# WifiNode_Pwr.net
KiCad netlist of a schematic drawn in Altium Designer
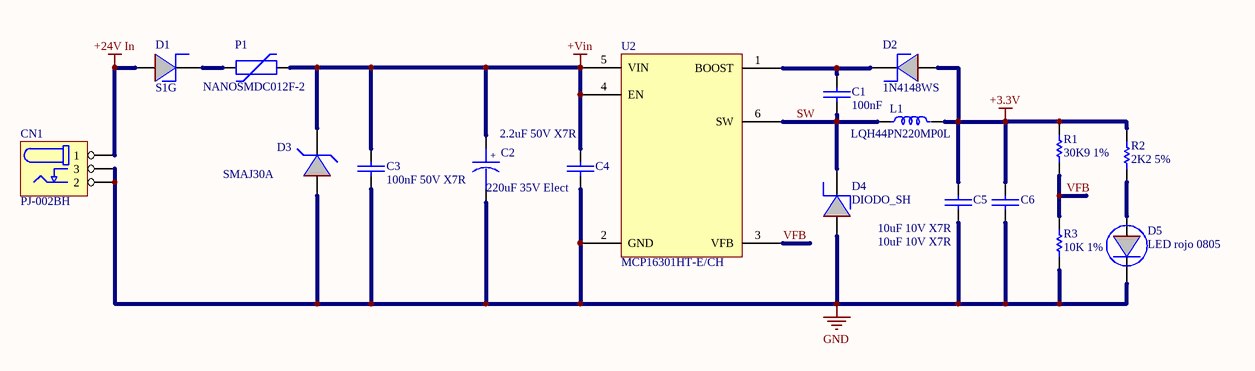
[diagram p0: WifiNode_Pwr.SchDoc]

(export (version "E")
  (design (tool "Eeschema 10.0.6"))
  (components
    (comp (ref "C1")
      (value "100nF")
      (footprint "C_0805")
      (description "Non Polarized Capacitor")
      (libsource (lib "WifiNode") (part "CAP"))
    )
    (comp (ref "C2")
      (value "220uF 35V Elect")
      (footprint "C_RAD_0.135_H_8X12_S")
      (description "Polarized Capacitor")
      (libsource (lib "WifiNode") (part "CAP_P"))
    )
    (comp (ref "C3")
      (value "100nF 50V X7R")
      (footprint "C_0805")
      (description "Non Polarized Capacitor")
      (libsource (lib "WifiNode") (part "CAP"))
    )
    (comp (ref "C4")
      (value "2.2uF 50V X7R")
      (footprint "C_0805")
      (description "Non Polarized Capacitor")
      (libsource (lib "WifiNode") (part "CAP"))
    )
    (comp (ref "C5")
      (value "10uF 10V X7R")
      (footprint "C_0805")
      (description "Non Polarized Capacitor")
      (libsource (lib "WifiNode") (part "CAP"))
    )
    (comp (ref "C6")
      (value "10uF 10V X7R")
      (footprint "C_0805")
      (description "Non Polarized Capacitor")
      (libsource (lib "WifiNode") (part "CAP"))
    )
    (comp (ref "CN1")
      (value "PJ-002BH")
      (footprint "PJ002B")
      (description "Barrel Power Connector")
      (libsource (lib "WifiNode") (part "CN_PowerJack"))
    )
    (comp (ref "D1")
      (value "S1G")
      (footprint "D_SMA")
      (description "Diode Shottky")
      (libsource (lib "") (part "DIODO_SH_1"))
    )
    (comp (ref "D2")
      (value "1N4148WS")
      (footprint "D_SMA")
      (description "Diode Shottky")
      (libsource (lib "WifiNode") (part "DIODO_SH"))
    )
    (comp (ref "D3")
      (value "SMAJ30A")
      (footprint "D_SMA")
      (description "Unidirectional TVS")
      (libsource (lib "WifiNode") (part "DIODE_TVS"))
    )
    (comp (ref "D4")
      (value "DIODO_SH")
      (footprint "D_SMA")
      (description "Diode Shottky")
      (libsource (lib "WifiNode") (part "DIODO_SH"))
    )
    (comp (ref "D5")
      (value "LED rojo 0805")
      (footprint "D_0805")
      (description "LED")
      (libsource (lib "WifiNode") (part "LED"))
    )
    (comp (ref "L1")
      (value "LQH44PN220MP0L")
      (footprint "LQH44")
      (description "Inductor")
      (libsource (lib "WifiNode") (part "IND"))
    )
    (comp (ref "P1")
      (value "NANOSMDC012F-2")
      (footprint "NANOSMDC")
      (description "Polyswitch")
      (libsource (lib "WifiNode") (part "PLYSW"))
    )
    (comp (ref "R1")
      (value "30K9 1%")
      (footprint "R_0805")
      (description "Resistor")
      (libsource (lib "WifiNode") (part "Res1"))
    )
    (comp (ref "R2")
      (value "2K2 5%")
      (footprint "R_0805")
      (description "Resistor")
      (libsource (lib "WifiNode") (part "Res1"))
    )
    (comp (ref "R3")
      (value "10K 1%")
      (footprint "R_0805")
      (description "Resistor")
      (libsource (lib "WifiNode") (part "Res1"))
    )
    (comp (ref "U2")
      (value "MCP16301HT-E/CH")
      (footprint "SOT23-6")
      (description "Buck 36V-adj 600mA SOT-6")
      (libsource (lib "WifiNode") (part "MCP16301"))
    )
  )
  (nets
    (net (code "1") (name "+3.3V") (class "Default")
      (node (ref "C5") (pin "1") (pinfunction "1_1") (pintype "passive"))
      (node (ref "C6") (pin "1") (pinfunction "1_1") (pintype "passive"))
      (node (ref "D2") (pin "1") (pinfunction "A_1") (pintype "passive"))
      (node (ref "L1") (pin "2") (pinfunction "2_2") (pintype "passive"))
      (node (ref "R1") (pin "2") (pinfunction "2_2") (pintype "passive"))
      (node (ref "R2") (pin "2") (pinfunction "2_2") (pintype "passive"))
    )
    (net (code "2") (name "+24V In") (class "Default")
      (node (ref "CN1") (pin "1") (pinfunction "1_1") (pintype "passive"))
      (node (ref "D1") (pin "1") (pinfunction "A_1") (pintype "passive"))
    )
    (net (code "3") (name "+Vin") (class "Default")
      (node (ref "C2") (pin "1") (pinfunction "1_1") (pintype "passive"))
      (node (ref "C3") (pin "1") (pinfunction "1_1") (pintype "passive"))
      (node (ref "C4") (pin "1") (pinfunction "1_1") (pintype "passive"))
      (node (ref "D3") (pin "2") (pinfunction "K_2") (pintype "passive"))
      (node (ref "P1") (pin "2") (pinfunction "2_2") (pintype "passive"))
      (node (ref "U2") (pin "4") (pinfunction "EN_4") (pintype "passive"))
      (node (ref "U2") (pin "5") (pinfunction "VIN_5") (pintype "passive"))
    )
    (net (code "4") (name "/SW") (class "Default")
      (node (ref "C1") (pin "2") (pinfunction "2_2") (pintype "passive"))
      (node (ref "D4") (pin "2") (pinfunction "K_2") (pintype "passive"))
      (node (ref "L1") (pin "1") (pinfunction "1_1") (pintype "passive"))
      (node (ref "U2") (pin "6") (pinfunction "SW_6") (pintype "passive"))
    )
    (net (code "5") (name "/VFB") (class "Default")
      (node (ref "R1") (pin "1") (pinfunction "1_1") (pintype "passive"))
      (node (ref "R3") (pin "2") (pinfunction "2_2") (pintype "passive"))
      (node (ref "U2") (pin "3") (pinfunction "VFB_3") (pintype "passive"))
    )
    (net (code "6") (name "GND") (class "Default")
      (node (ref "C2") (pin "2") (pinfunction "2_2") (pintype "passive"))
      (node (ref "C3") (pin "2") (pinfunction "2_2") (pintype "passive"))
      (node (ref "C4") (pin "2") (pinfunction "2_2") (pintype "passive"))
      (node (ref "C5") (pin "2") (pinfunction "2_2") (pintype "passive"))
      (node (ref "C6") (pin "2") (pinfunction "2_2") (pintype "passive"))
      (node (ref "CN1") (pin "2") (pinfunction "2_2") (pintype "passive"))
      (node (ref "CN1") (pin "3") (pinfunction "3_3") (pintype "passive"))
      (node (ref "D3") (pin "1") (pinfunction "A_1") (pintype "passive"))
      (node (ref "D4") (pin "1") (pinfunction "A_1") (pintype "passive"))
      (node (ref "D5") (pin "2") (pinfunction "K_2") (pintype "passive"))
      (node (ref "R3") (pin "1") (pinfunction "1_1") (pintype "passive"))
      (node (ref "U2") (pin "2") (pinfunction "GND_2") (pintype "passive"))
    )
    (net (code "7") (name "Net-(D1-K)") (class "Default")
      (node (ref "D1") (pin "2") (pinfunction "K_2") (pintype "passive"))
      (node (ref "P1") (pin "1") (pinfunction "1_1") (pintype "passive"))
    )
    (net (code "8") (name "Net-(D2-K)") (class "Default")
      (node (ref "C1") (pin "1") (pinfunction "1_1") (pintype "passive"))
      (node (ref "D2") (pin "2") (pinfunction "K_2") (pintype "passive"))
      (node (ref "U2") (pin "1") (pinfunction "BOOST_1") (pintype "passive"))
    )
    (net (code "9") (name "Net-(D5-A)") (class "Default")
      (node (ref "D5") (pin "1") (pinfunction "A_1") (pintype "passive"))
      (node (ref "R2") (pin "1") (pinfunction "1_1") (pintype "passive"))
    )
  )
)
